# USB_Outputs.net
KiCad netlist of a schematic drawn in Altium Designer
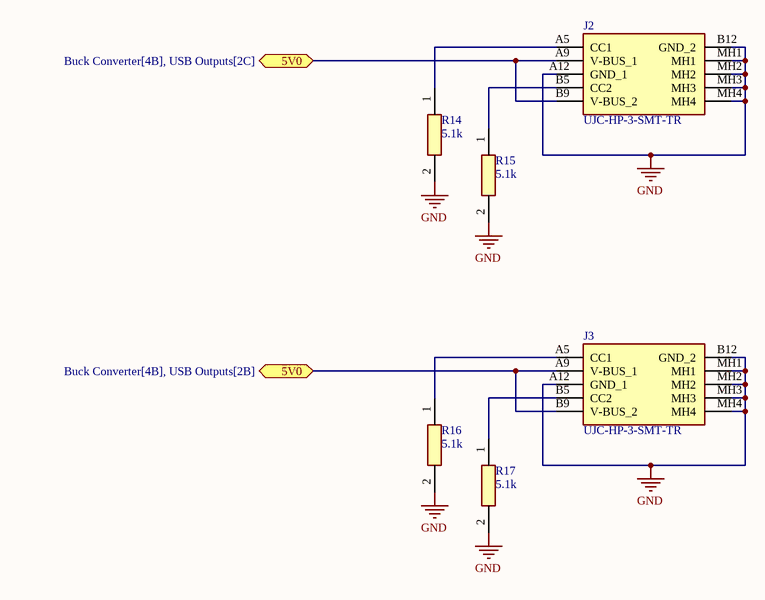
[diagram p0: USB Outputs.SchDoc]

(export (version "E")
  (design (tool "Eeschema 10.0.6"))
  (components
    (comp (ref "J2")
      (value "UJC-HP-3-SMT-TR")
      (footprint "SamacSys:UJCHP3SMTTR")
      (description "Connector")
      (fields (field (name "MOUSER PART NUMBER") "490-UJC-HP-3-SMT-TR"))
      (libsource (lib "*") (part "UJC-HP-3-SMT-TR"))
    )
    (comp (ref "J3")
      (value "UJC-HP-3-SMT-TR")
      (footprint "SamacSys:UJCHP3SMTTR")
      (description "Connector")
      (fields (field (name "MOUSER PART NUMBER") "490-UJC-HP-3-SMT-TR"))
      (libsource (lib "*") (part "UJC-HP-3-SMT-TR"))
    )
    (comp (ref "R14")
      (value "5.1k")
      (footprint "SamacSys:RESC2012X60N")
      (description "Resistor")
      (fields
        (field (name "MANUFACTURER_PART_NUMBER") "RC0805FR-075K1L")
        (field (name "MOUSER PART NUMBER") "603-RC0805FR-075K1L")
      )
      (libsource (lib "*") (part "RC0805FR-075K1L"))
    )
    (comp (ref "R15")
      (value "5.1k")
      (footprint "SamacSys:RESC2012X60N")
      (description "Resistor")
      (fields
        (field (name "MANUFACTURER_PART_NUMBER") "RC0805FR-075K1L")
        (field (name "MOUSER PART NUMBER") "603-RC0805FR-075K1L")
      )
      (libsource (lib "*") (part "RC0805FR-075K1L"))
    )
    (comp (ref "R16")
      (value "5.1k")
      (footprint "SamacSys:RESC2012X60N")
      (description "Resistor")
      (fields
        (field (name "MANUFACTURER_PART_NUMBER") "RC0805FR-075K1L")
        (field (name "MOUSER PART NUMBER") "603-RC0805FR-075K1L")
      )
      (libsource (lib "*") (part "RC0805FR-075K1L"))
    )
    (comp (ref "R17")
      (value "5.1k")
      (footprint "SamacSys:RESC2012X60N")
      (description "Resistor")
      (fields
        (field (name "MANUFACTURER_PART_NUMBER") "RC0805FR-075K1L")
        (field (name "MOUSER PART NUMBER") "603-RC0805FR-075K1L")
      )
      (libsource (lib "*") (part "RC0805FR-075K1L"))
    )
  )
  (nets
    (net (code "1") (name "/5V0") (class "Default")
      (node (ref "J2") (pin "A9") (pinfunction "V-BUS_1_A9") (pintype "passive"))
      (node (ref "J2") (pin "B9") (pinfunction "V-BUS_2_B9") (pintype "passive"))
      (node (ref "J3") (pin "A9") (pinfunction "V-BUS_1_A9") (pintype "passive"))
      (node (ref "J3") (pin "B9") (pinfunction "V-BUS_2_B9") (pintype "passive"))
    )
    (net (code "2") (name "GND") (class "Default")
      (node (ref "J2") (pin "A12") (pinfunction "GND_1_A12") (pintype "passive"))
      (node (ref "J2") (pin "B12") (pinfunction "GND_2_B12") (pintype "passive"))
      (node (ref "J2") (pin "MH1") (pinfunction "MH1_MH1") (pintype "passive"))
      (node (ref "J2") (pin "MH2") (pinfunction "MH2_MH2") (pintype "passive"))
      (node (ref "J2") (pin "MH3") (pinfunction "MH3_MH3") (pintype "passive"))
      (node (ref "J2") (pin "MH4") (pinfunction "MH4_MH4") (pintype "passive"))
      (node (ref "J3") (pin "A12") (pinfunction "GND_1_A12") (pintype "passive"))
      (node (ref "J3") (pin "B12") (pinfunction "GND_2_B12") (pintype "passive"))
      (node (ref "J3") (pin "MH1") (pinfunction "MH1_MH1") (pintype "passive"))
      (node (ref "J3") (pin "MH2") (pinfunction "MH2_MH2") (pintype "passive"))
      (node (ref "J3") (pin "MH3") (pinfunction "MH3_MH3") (pintype "passive"))
      (node (ref "J3") (pin "MH4") (pinfunction "MH4_MH4") (pintype "passive"))
      (node (ref "R14") (pin "2") (pinfunction "2_2") (pintype "passive"))
      (node (ref "R15") (pin "2") (pinfunction "2_2") (pintype "passive"))
      (node (ref "R16") (pin "2") (pinfunction "2_2") (pintype "passive"))
      (node (ref "R17") (pin "2") (pinfunction "2_2") (pintype "passive"))
    )
    (net (code "3") (name "Net-(J2-CC1)") (class "Default")
      (node (ref "J2") (pin "A5") (pinfunction "CC1_A5") (pintype "passive"))
      (node (ref "R14") (pin "1") (pinfunction "1_1") (pintype "passive"))
    )
    (net (code "4") (name "Net-(J2-CC2)") (class "Default")
      (node (ref "J2") (pin "B5") (pinfunction "CC2_B5") (pintype "passive"))
      (node (ref "R15") (pin "1") (pinfunction "1_1") (pintype "passive"))
    )
    (net (code "5") (name "Net-(J3-CC1)") (class "Default")
      (node (ref "J3") (pin "A5") (pinfunction "CC1_A5") (pintype "passive"))
      (node (ref "R16") (pin "1") (pinfunction "1_1") (pintype "passive"))
    )
    (net (code "6") (name "Net-(J3-CC2)") (class "Default")
      (node (ref "J3") (pin "B5") (pinfunction "CC2_B5") (pintype "passive"))
      (node (ref "R17") (pin "1") (pinfunction "1_1") (pintype "passive"))
    )
  )
)
